# design.net
KiCad netlist of a schematic drawn in Altium Designer
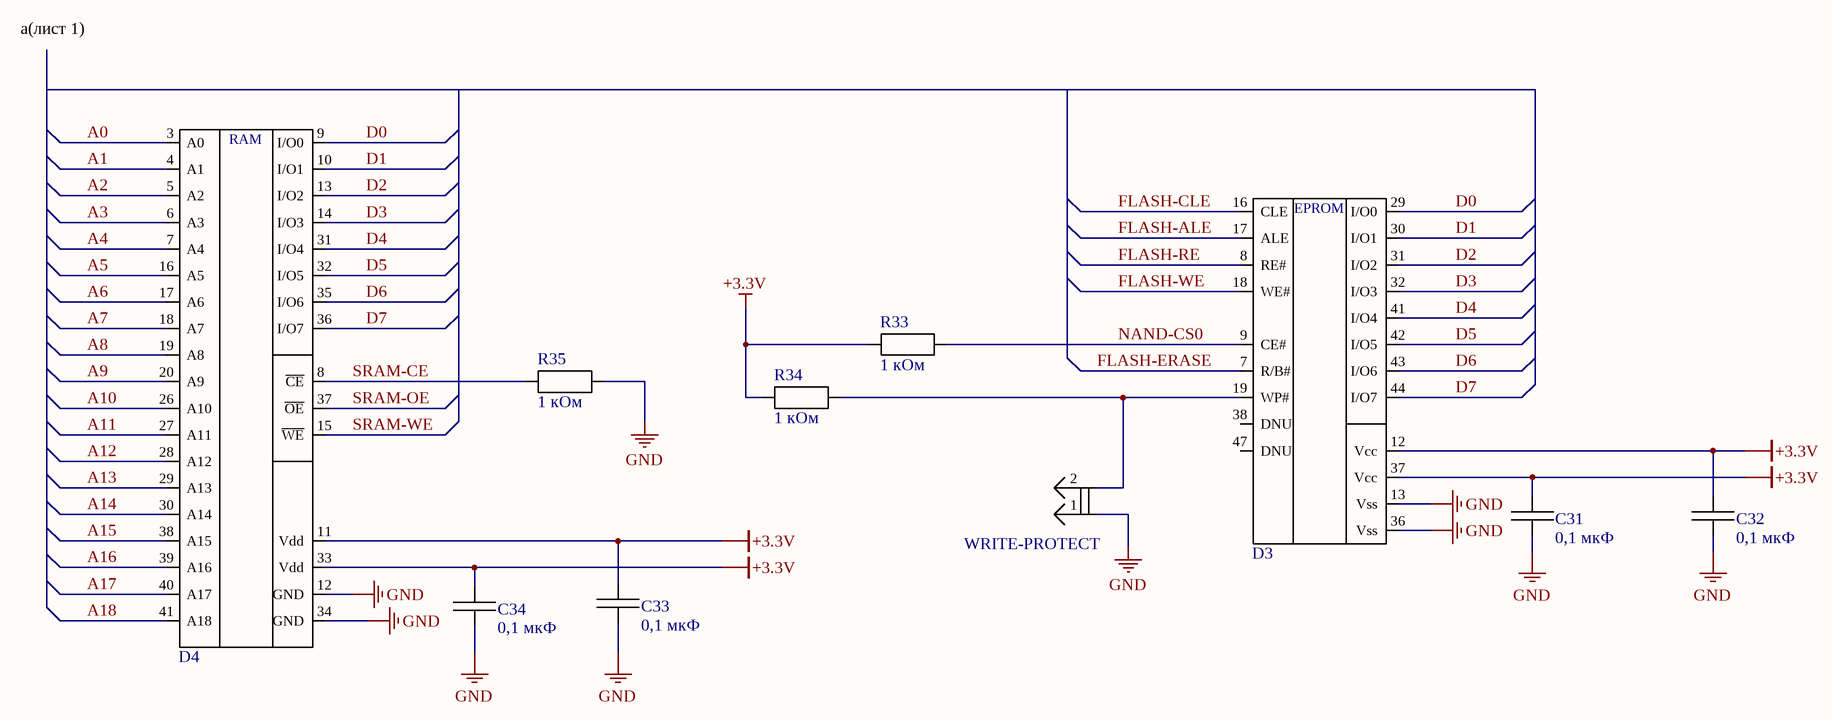
[diagram p0: Память.SchDoc]

(export (version "E")
  (design (tool "Eeschema 10.0.6"))
  (components
    (comp (ref "C31")
      (value "0,1 мкФ")
      (footprint "0603-AVX")
      (fields
        (field (name "MANUFACTURER") "AVX")
        (field (name "MANUFACTURERPARTNUMBER") "0603YC104KAT2A")
        (field (name "TOLERANCE") "±10%")
      )
      (libsource (lib "КОНДЕНСАТОРЫ") (part "0603-X7R-0,1мкФ-16В-10%"))
    )
    (comp (ref "C32")
      (value "0,1 мкФ")
      (footprint "0603-AVX")
      (fields
        (field (name "MANUFACTURER") "AVX")
        (field (name "MANUFACTURERPARTNUMBER") "0603YC104KAT2A")
        (field (name "TOLERANCE") "±10%")
      )
      (libsource (lib "КОНДЕНСАТОРЫ") (part "0603-X7R-0,1мкФ-16В-10%"))
    )
    (comp (ref "C33")
      (value "0,1 мкФ")
      (footprint "0603-AVX")
      (fields
        (field (name "MANUFACTURER") "AVX")
        (field (name "MANUFACTURERPARTNUMBER") "0603YC104KAT2A")
        (field (name "TOLERANCE") "±10%")
      )
      (libsource (lib "КОНДЕНСАТОРЫ") (part "0603-X7R-0,1мкФ-16В-10%"))
    )
    (comp (ref "C34")
      (value "0,1 мкФ")
      (footprint "0603-AVX")
      (fields
        (field (name "MANUFACTURER") "AVX")
        (field (name "MANUFACTURERPARTNUMBER") "0603YC104KAT2A")
        (field (name "TOLERANCE") "±10%")
      )
      (libsource (lib "КОНДЕНСАТОРЫ") (part "0603-X7R-0,1мкФ-16В-10%"))
    )
    (comp (ref "D3")
      (value "~")
      (footprint "TSOP_48(TYPE_1,CPL)")
      (fields
        (field (name "MANUFACTURERPARTNUMBER") "MT29F2G08ABAEAWP IT")
        (field (name "MANUFACTURER") "Micron")
      )
      (libsource (lib "МИКРОСХЕМЫ") (part "MT29F2G08ABAEAWPIT"))
    )
    (comp (ref "D4")
      (value "~")
      (footprint "TSOP-44")
      (description "RAM память")
      (fields
        (field (name "MANUFACTURERPARTNUMBER") "IS61WV5128BLL-10TLI")
        (field (name "MANUFACTURER") "Micron")
      )
      (libsource (lib "МИКРОСХЕМЫ") (part "IS61WV5128BLL-10TLI"))
    )
    (comp (ref "R33")
      (value "1 кОм")
      (footprint "Р1-12-0,125")
      (fields
        (field (name "TOLERANCE") "±1%-Л")
        (field (name "PARTNUMBER") "АЛЯР.434110.005 ТУ")
        (field (name "MANUFACTURERPARTNUMBER") "Р1-12-0,125-10,0 кОм±1%-Л")
      )
      (libsource (lib "РЕЗИСТОРЫ") (part "Р1-12-0,125-10,0 кОм±1%"))
    )
    (comp (ref "R34")
      (value "1 кОм")
      (footprint "Р1-12-0,125")
      (fields
        (field (name "TOLERANCE") "±1%-Л")
        (field (name "PARTNUMBER") "АЛЯР.434110.005 ТУ")
        (field (name "MANUFACTURERPARTNUMBER") "Р1-12-0,125-10,0 кОм±1%-Л")
      )
      (libsource (lib "РЕЗИСТОРЫ") (part "Р1-12-0,125-10,0 кОм±1%"))
    )
    (comp (ref "R35")
      (value "1 кОм")
      (footprint "Р1-12-0,125")
      (fields
        (field (name "TOLERANCE") "±1%-Л")
        (field (name "PARTNUMBER") "АЛЯР.434110.005 ТУ")
        (field (name "MANUFACTURERPARTNUMBER") "Р1-12-0,125-10,0 кОм±1%-Л")
      )
      (libsource (lib "РЕЗИСТОРЫ") (part "Р1-12-0,125-10,0 кОм±1%"))
    )
    (comp (ref "WRITE-PROTECT")
      (value "~")
      (footprint "СНП346-2ВП21-1")
      (fields
        (field (name "MANUFACTURERPARTNUMBER") "Вилка СНП346-2ВП21-1")
        (field (name "PARTNUMBER") "РЮМК.430420.011ТУ")
      )
      (libsource (lib "РАЗЪЕМЫ") (part "СНП346-2ВП21-1"))
    )
  )
  (nets
    (net (code "1") (name "+3.3V") (class "Default")
      (node (ref "C31") (pin "2") (pinfunction "2_2") (pintype "passive"))
      (node (ref "C32") (pin "2") (pinfunction "2_2") (pintype "passive"))
      (node (ref "C33") (pin "2") (pinfunction "2_2") (pintype "passive"))
      (node (ref "C34") (pin "2") (pinfunction "2_2") (pintype "passive"))
      (node (ref "D3") (pin "12") (pinfunction "Vcc_12") (pintype "passive"))
      (node (ref "D3") (pin "37") (pinfunction "Vcc_37") (pintype "passive"))
      (node (ref "D4") (pin "11") (pinfunction "Vdd_11") (pintype "passive"))
      (node (ref "D4") (pin "33") (pinfunction "Vdd_33") (pintype "passive"))
      (node (ref "R33") (pin "2") (pinfunction "2_2") (pintype "passive"))
      (node (ref "R34") (pin "2") (pinfunction "2_2") (pintype "passive"))
    )
    (net (code "2") (name "/A0") (class "Default")
      (node (ref "D4") (pin "3") (pinfunction "A0_3") (pintype "passive"))
    )
    (net (code "3") (name "/A1") (class "Default")
      (node (ref "D4") (pin "4") (pinfunction "A1_4") (pintype "passive"))
    )
    (net (code "4") (name "/A2") (class "Default")
      (node (ref "D4") (pin "5") (pinfunction "A2_5") (pintype "passive"))
    )
    (net (code "5") (name "/A3") (class "Default")
      (node (ref "D4") (pin "6") (pinfunction "A3_6") (pintype "passive"))
    )
    (net (code "6") (name "/A4") (class "Default")
      (node (ref "D4") (pin "7") (pinfunction "A4_7") (pintype "passive"))
    )
    (net (code "7") (name "/A5") (class "Default")
      (node (ref "D4") (pin "16") (pinfunction "A5_16") (pintype "passive"))
    )
    (net (code "8") (name "/A6") (class "Default")
      (node (ref "D4") (pin "17") (pinfunction "A6_17") (pintype "passive"))
    )
    (net (code "9") (name "/A7") (class "Default")
      (node (ref "D4") (pin "18") (pinfunction "A7_18") (pintype "passive"))
    )
    (net (code "10") (name "/A8") (class "Default")
      (node (ref "D4") (pin "19") (pinfunction "A8_19") (pintype "passive"))
    )
    (net (code "11") (name "/A9") (class "Default")
      (node (ref "D4") (pin "20") (pinfunction "A9_20") (pintype "passive"))
    )
    (net (code "12") (name "/A10") (class "Default")
      (node (ref "D4") (pin "26") (pinfunction "A10_26") (pintype "passive"))
    )
    (net (code "13") (name "/A11") (class "Default")
      (node (ref "D4") (pin "27") (pinfunction "A11_27") (pintype "passive"))
    )
    (net (code "14") (name "/A12") (class "Default")
      (node (ref "D4") (pin "28") (pinfunction "A12_28") (pintype "passive"))
    )
    (net (code "15") (name "/A13") (class "Default")
      (node (ref "D4") (pin "29") (pinfunction "A13_29") (pintype "passive"))
    )
    (net (code "16") (name "/A14") (class "Default")
      (node (ref "D4") (pin "30") (pinfunction "A14_30") (pintype "passive"))
    )
    (net (code "17") (name "/A15") (class "Default")
      (node (ref "D4") (pin "38") (pinfunction "A15_38") (pintype "passive"))
    )
    (net (code "18") (name "/A16") (class "Default")
      (node (ref "D4") (pin "39") (pinfunction "A16_39") (pintype "passive"))
    )
    (net (code "19") (name "/A17") (class "Default")
      (node (ref "D4") (pin "40") (pinfunction "A17_40") (pintype "passive"))
    )
    (net (code "20") (name "/A18") (class "Default")
      (node (ref "D4") (pin "41") (pinfunction "A18_41") (pintype "passive"))
    )
    (net (code "21") (name "/D0") (class "Default")
      (node (ref "D3") (pin "29") (pinfunction "I/O0_29") (pintype "passive"))
      (node (ref "D4") (pin "9") (pinfunction "I/O0_9") (pintype "passive"))
    )
    (net (code "22") (name "/D1") (class "Default")
      (node (ref "D3") (pin "30") (pinfunction "I/O1_30") (pintype "passive"))
      (node (ref "D4") (pin "10") (pinfunction "I/O1_10") (pintype "passive"))
    )
    (net (code "23") (name "/D2") (class "Default")
      (node (ref "D3") (pin "31") (pinfunction "I/O2_31") (pintype "passive"))
      (node (ref "D4") (pin "13") (pinfunction "I/O2_13") (pintype "passive"))
    )
    (net (code "24") (name "/D3") (class "Default")
      (node (ref "D3") (pin "32") (pinfunction "I/O3_32") (pintype "passive"))
      (node (ref "D4") (pin "14") (pinfunction "I/O3_14") (pintype "passive"))
    )
    (net (code "25") (name "/D4") (class "Default")
      (node (ref "D3") (pin "41") (pinfunction "I/O4_41") (pintype "passive"))
      (node (ref "D4") (pin "31") (pinfunction "I/O4_31") (pintype "passive"))
    )
    (net (code "26") (name "/D5") (class "Default")
      (node (ref "D3") (pin "42") (pinfunction "I/O5_42") (pintype "passive"))
      (node (ref "D4") (pin "32") (pinfunction "I/O5_32") (pintype "passive"))
    )
    (net (code "27") (name "/D6") (class "Default")
      (node (ref "D3") (pin "43") (pinfunction "I/O6_43") (pintype "passive"))
      (node (ref "D4") (pin "35") (pinfunction "I/O6_35") (pintype "passive"))
    )
    (net (code "28") (name "/D7") (class "Default")
      (node (ref "D3") (pin "44") (pinfunction "I/O7_44") (pintype "passive"))
      (node (ref "D4") (pin "36") (pinfunction "I/O7_36") (pintype "passive"))
    )
    (net (code "29") (name "/FLASH-ALE") (class "Default")
      (node (ref "D3") (pin "17") (pinfunction "ALE_17") (pintype "passive"))
    )
    (net (code "30") (name "/FLASH-CLE") (class "Default")
      (node (ref "D3") (pin "16") (pinfunction "CLE_16") (pintype "passive"))
    )
    (net (code "31") (name "/FLASH-ERASE") (class "Default")
      (node (ref "D3") (pin "7") (pinfunction "R/B#_7") (pintype "passive"))
    )
    (net (code "32") (name "/FLASH-RE") (class "Default")
      (node (ref "D3") (pin "8") (pinfunction "RE#_8") (pintype "passive"))
    )
    (net (code "33") (name "/FLASH-WE") (class "Default")
      (node (ref "D3") (pin "18") (pinfunction "WE#_18") (pintype "passive"))
    )
    (net (code "34") (name "/NAND-CS0") (class "Default")
      (node (ref "D3") (pin "9") (pinfunction "CE#_9") (pintype "passive"))
      (node (ref "R33") (pin "1") (pinfunction "1_1") (pintype "passive"))
    )
    (net (code "35") (name "/SRAM-CE") (class "Default")
      (node (ref "D4") (pin "8") (pinfunction "~{CE}_8") (pintype "passive"))
      (node (ref "R35") (pin "1") (pinfunction "1_1") (pintype "passive"))
    )
    (net (code "36") (name "/SRAM-OE") (class "Default")
      (node (ref "D4") (pin "37") (pinfunction "~{OE}_37") (pintype "passive"))
    )
    (net (code "37") (name "/SRAM-WE") (class "Default")
      (node (ref "D4") (pin "15") (pinfunction "~{WE}_15") (pintype "passive"))
    )
    (net (code "38") (name "GND") (class "Default")
      (node (ref "C31") (pin "1") (pinfunction "1_1") (pintype "passive"))
      (node (ref "C32") (pin "1") (pinfunction "1_1") (pintype "passive"))
      (node (ref "C33") (pin "1") (pinfunction "1_1") (pintype "passive"))
      (node (ref "C34") (pin "1") (pinfunction "1_1") (pintype "passive"))
      (node (ref "D3") (pin "13") (pinfunction "Vss_13") (pintype "passive"))
      (node (ref "D3") (pin "36") (pinfunction "Vss_36") (pintype "passive"))
      (node (ref "D4") (pin "12") (pinfunction "GND_12") (pintype "passive"))
      (node (ref "D4") (pin "34") (pinfunction "GND_34") (pintype "passive"))
      (node (ref "R35") (pin "2") (pinfunction "2_2") (pintype "passive"))
      (node (ref "WRITE-PROTECT") (pin "1") (pinfunction "1_1") (pintype "passive"))
    )
    (net (code "39") (name "Net-(D3-WP#)") (class "Default")
      (node (ref "D3") (pin "19") (pinfunction "WP#_19") (pintype "passive"))
      (node (ref "R34") (pin "1") (pinfunction "1_1") (pintype "passive"))
      (node (ref "WRITE-PROTECT") (pin "2") (pinfunction "2_2") (pintype "passive"))
    )
    (net (code "40") (name "unconnected-(D3-DNU-Pad38)") (class "Default")
      (node (ref "D3") (pin "38") (pinfunction "DNU_38") (pintype "passive"))
    )
    (net (code "41") (name "unconnected-(D3-DNU-Pad47)") (class "Default")
      (node (ref "D3") (pin "47") (pinfunction "DNU_47") (pintype "passive"))
    )
    (net (code "42") (name "unconnected-(D3-NC-Pad1)") (class "Default")
      (node (ref "D3") (pin "1") (pinfunction "NC_1") (pintype "passive"))
    )
    (net (code "43") (name "unconnected-(D3-NC-Pad2)") (class "Default")
      (node (ref "D3") (pin "2") (pinfunction "NC_2") (pintype "passive"))
    )
    (net (code "44") (name "unconnected-(D3-NC-Pad3)") (class "Default")
      (node (ref "D3") (pin "3") (pinfunction "NC_3") (pintype "passive"))
    )
    (net (code "45") (name "unconnected-(D3-NC-Pad4)") (class "Default")
      (node (ref "D3") (pin "4") (pinfunction "NC_4") (pintype "passive"))
    )
    (net (code "46") (name "unconnected-(D3-NC-Pad5)") (class "Default")
      (node (ref "D3") (pin "5") (pinfunction "NC_5") (pintype "passive"))
    )
    (net (code "47") (name "unconnected-(D3-NC-Pad6)") (class "Default")
      (node (ref "D3") (pin "6") (pinfunction "NC_6") (pintype "passive"))
    )
    (net (code "48") (name "unconnected-(D3-NC-Pad10)") (class "Default")
      (node (ref "D3") (pin "10") (pinfunction "NC_10") (pintype "passive"))
    )
    (net (code "49") (name "unconnected-(D3-NC-Pad11)") (class "Default")
      (node (ref "D3") (pin "11") (pinfunction "NC_11") (pintype "passive"))
    )
    (net (code "50") (name "unconnected-(D3-NC-Pad14)") (class "Default")
      (node (ref "D3") (pin "14") (pinfunction "NC_14") (pintype "passive"))
    )
    (net (code "51") (name "unconnected-(D3-NC-Pad15)") (class "Default")
      (node (ref "D3") (pin "15") (pinfunction "NC_15") (pintype "passive"))
    )
    (net (code "52") (name "unconnected-(D3-NC-Pad20)") (class "Default")
      (node (ref "D3") (pin "20") (pinfunction "NC_20") (pintype "passive"))
    )
    (net (code "53") (name "unconnected-(D3-NC-Pad21)") (class "Default")
      (node (ref "D3") (pin "21") (pinfunction "NC_21") (pintype "passive"))
    )
    (net (code "54") (name "unconnected-(D3-NC-Pad22)") (class "Default")
      (node (ref "D3") (pin "22") (pinfunction "NC_22") (pintype "passive"))
    )
    (net (code "55") (name "unconnected-(D3-NC-Pad23)") (class "Default")
      (node (ref "D3") (pin "23") (pinfunction "NC_23") (pintype "passive"))
    )
    (net (code "56") (name "unconnected-(D3-NC-Pad24)") (class "Default")
      (node (ref "D3") (pin "24") (pinfunction "NC_24") (pintype "passive"))
    )
    (net (code "57") (name "unconnected-(D3-NC-Pad25)") (class "Default")
      (node (ref "D3") (pin "25") (pinfunction "NC_25") (pintype "passive"))
    )
    (net (code "58") (name "unconnected-(D3-NC-Pad26)") (class "Default")
      (node (ref "D3") (pin "26") (pinfunction "NC_26") (pintype "passive"))
    )
    (net (code "59") (name "unconnected-(D3-NC-Pad27)") (class "Default")
      (node (ref "D3") (pin "27") (pinfunction "NC_27") (pintype "passive"))
    )
    (net (code "60") (name "unconnected-(D3-NC-Pad28)") (class "Default")
      (node (ref "D3") (pin "28") (pinfunction "NC_28") (pintype "passive"))
    )
    (net (code "61") (name "unconnected-(D3-NC-Pad33)") (class "Default")
      (node (ref "D3") (pin "33") (pinfunction "NC_33") (pintype "passive"))
    )
    (net (code "62") (name "unconnected-(D3-NC-Pad34)") (class "Default")
      (node (ref "D3") (pin "34") (pinfunction "NC_34") (pintype "passive"))
    )
    (net (code "63") (name "unconnected-(D3-NC-Pad35)") (class "Default")
      (node (ref "D3") (pin "35") (pinfunction "NC_35") (pintype "passive"))
    )
    (net (code "64") (name "unconnected-(D3-NC-Pad39)") (class "Default")
      (node (ref "D3") (pin "39") (pinfunction "NC_39") (pintype "passive"))
    )
    (net (code "65") (name "unconnected-(D3-NC-Pad40)") (class "Default")
      (node (ref "D3") (pin "40") (pinfunction "NC_40") (pintype "passive"))
    )
    (net (code "66") (name "unconnected-(D3-NC-Pad45)") (class "Default")
      (node (ref "D3") (pin "45") (pinfunction "NC_45") (pintype "passive"))
    )
    (net (code "67") (name "unconnected-(D3-NC-Pad46)") (class "Default")
      (node (ref "D3") (pin "46") (pinfunction "NC_46") (pintype "passive"))
    )
    (net (code "68") (name "unconnected-(D3-NC-Pad48)") (class "Default")
      (node (ref "D3") (pin "48") (pinfunction "NC_48") (pintype "passive"))
    )
    (net (code "69") (name "unconnected-(D4-NC-Pad1)") (class "Default")
      (node (ref "D4") (pin "1") (pinfunction "NC_1") (pintype "passive"))
    )
    (net (code "70") (name "unconnected-(D4-NC-Pad2)") (class "Default")
      (node (ref "D4") (pin "2") (pinfunction "NC_2") (pintype "passive"))
    )
    (net (code "71") (name "unconnected-(D4-NC-Pad21)") (class "Default")
      (node (ref "D4") (pin "21") (pinfunction "NC_21") (pintype "passive"))
    )
    (net (code "72") (name "unconnected-(D4-NC-Pad22)") (class "Default")
      (node (ref "D4") (pin "22") (pinfunction "NC_22") (pintype "passive"))
    )
    (net (code "73") (name "unconnected-(D4-NC-Pad23)") (class "Default")
      (node (ref "D4") (pin "23") (pinfunction "NC_23") (pintype "passive"))
    )
    (net (code "74") (name "unconnected-(D4-NC-Pad24)") (class "Default")
      (node (ref "D4") (pin "24") (pinfunction "NC_24") (pintype "passive"))
    )
    (net (code "75") (name "unconnected-(D4-NC-Pad25)") (class "Default")
      (node (ref "D4") (pin "25") (pinfunction "NC_25") (pintype "passive"))
    )
    (net (code "76") (name "unconnected-(D4-NC-Pad42)") (class "Default")
      (node (ref "D4") (pin "42") (pinfunction "NC_42") (pintype "passive"))
    )
    (net (code "77") (name "unconnected-(D4-NC-Pad43)") (class "Default")
      (node (ref "D4") (pin "43") (pinfunction "NC_43") (pintype "passive"))
    )
    (net (code "78") (name "unconnected-(D4-NC-Pad44)") (class "Default")
      (node (ref "D4") (pin "44") (pinfunction "NC_44") (pintype "passive"))
    )
  )
)
